# eib.net
KiCad netlist of a schematic drawn in EAGLE
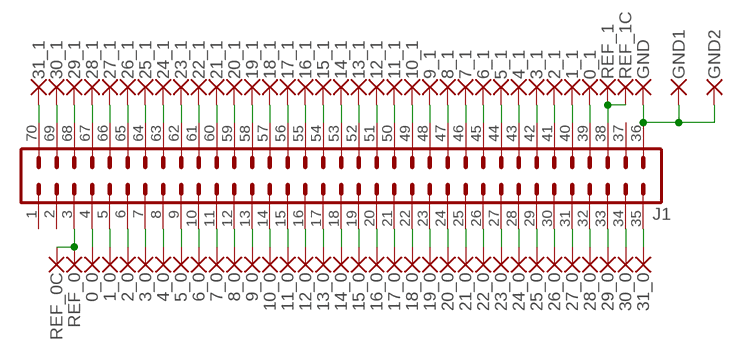
[diagram p0: schematic, sheet 1]

(export (version "E")
  (design (tool "Eeschema 10.0.6"))
  (components
    (comp (ref "0_0")
      (value "PAD_20_37")
      (footprint "eagle-import:PAD_20_37")
      (libsource (lib "eagle-import") (part "PAD_20_37"))
    )
    (comp (ref "0_1")
      (value "PAD_20_37")
      (footprint "eagle-import:PAD_20_37")
      (libsource (lib "eagle-import") (part "PAD_20_37"))
    )
    (comp (ref "1_0")
      (value "PAD_20_37")
      (footprint "eagle-import:PAD_20_37")
      (libsource (lib "eagle-import") (part "PAD_20_37"))
    )
    (comp (ref "1_1")
      (value "PAD_20_37")
      (footprint "eagle-import:PAD_20_37")
      (libsource (lib "eagle-import") (part "PAD_20_37"))
    )
    (comp (ref "2_0")
      (value "PAD_20_37")
      (footprint "eagle-import:PAD_20_37")
      (libsource (lib "eagle-import") (part "PAD_20_37"))
    )
    (comp (ref "2_1")
      (value "PAD_20_37")
      (footprint "eagle-import:PAD_20_37")
      (libsource (lib "eagle-import") (part "PAD_20_37"))
    )
    (comp (ref "3_0")
      (value "PAD_20_37")
      (footprint "eagle-import:PAD_20_37")
      (libsource (lib "eagle-import") (part "PAD_20_37"))
    )
    (comp (ref "3_1")
      (value "PAD_20_37")
      (footprint "eagle-import:PAD_20_37")
      (libsource (lib "eagle-import") (part "PAD_20_37"))
    )
    (comp (ref "4_0")
      (value "PAD_20_37")
      (footprint "eagle-import:PAD_20_37")
      (libsource (lib "eagle-import") (part "PAD_20_37"))
    )
    (comp (ref "4_1")
      (value "PAD_20_37")
      (footprint "eagle-import:PAD_20_37")
      (libsource (lib "eagle-import") (part "PAD_20_37"))
    )
    (comp (ref "5_0")
      (value "PAD_20_37")
      (footprint "eagle-import:PAD_20_37")
      (libsource (lib "eagle-import") (part "PAD_20_37"))
    )
    (comp (ref "5_1")
      (value "PAD_20_37")
      (footprint "eagle-import:PAD_20_37")
      (libsource (lib "eagle-import") (part "PAD_20_37"))
    )
    (comp (ref "6_0")
      (value "PAD_20_37")
      (footprint "eagle-import:PAD_20_37")
      (libsource (lib "eagle-import") (part "PAD_20_37"))
    )
    (comp (ref "6_1")
      (value "PAD_20_37")
      (footprint "eagle-import:PAD_20_37")
      (libsource (lib "eagle-import") (part "PAD_20_37"))
    )
    (comp (ref "7_0")
      (value "PAD_20_37")
      (footprint "eagle-import:PAD_20_37")
      (libsource (lib "eagle-import") (part "PAD_20_37"))
    )
    (comp (ref "7_1")
      (value "PAD_20_37")
      (footprint "eagle-import:PAD_20_37")
      (libsource (lib "eagle-import") (part "PAD_20_37"))
    )
    (comp (ref "8_0")
      (value "PAD_20_37")
      (footprint "eagle-import:PAD_20_37")
      (libsource (lib "eagle-import") (part "PAD_20_37"))
    )
    (comp (ref "8_1")
      (value "PAD_20_37")
      (footprint "eagle-import:PAD_20_37")
      (libsource (lib "eagle-import") (part "PAD_20_37"))
    )
    (comp (ref "9_0")
      (value "PAD_20_37")
      (footprint "eagle-import:PAD_20_37")
      (libsource (lib "eagle-import") (part "PAD_20_37"))
    )
    (comp (ref "9_1")
      (value "PAD_20_37")
      (footprint "eagle-import:PAD_20_37")
      (libsource (lib "eagle-import") (part "PAD_20_37"))
    )
    (comp (ref "10_0")
      (value "PAD_20_37")
      (footprint "eagle-import:PAD_20_37")
      (libsource (lib "eagle-import") (part "PAD_20_37"))
    )
    (comp (ref "10_1")
      (value "PAD_20_37")
      (footprint "eagle-import:PAD_20_37")
      (libsource (lib "eagle-import") (part "PAD_20_37"))
    )
    (comp (ref "11_0")
      (value "PAD_20_37")
      (footprint "eagle-import:PAD_20_37")
      (libsource (lib "eagle-import") (part "PAD_20_37"))
    )
    (comp (ref "11_1")
      (value "PAD_20_37")
      (footprint "eagle-import:PAD_20_37")
      (libsource (lib "eagle-import") (part "PAD_20_37"))
    )
    (comp (ref "12_0")
      (value "PAD_20_37")
      (footprint "eagle-import:PAD_20_37")
      (libsource (lib "eagle-import") (part "PAD_20_37"))
    )
    (comp (ref "12_1")
      (value "PAD_20_37")
      (footprint "eagle-import:PAD_20_37")
      (libsource (lib "eagle-import") (part "PAD_20_37"))
    )
    (comp (ref "13_0")
      (value "PAD_20_37")
      (footprint "eagle-import:PAD_20_37")
      (libsource (lib "eagle-import") (part "PAD_20_37"))
    )
    (comp (ref "13_1")
      (value "PAD_20_37")
      (footprint "eagle-import:PAD_20_37")
      (libsource (lib "eagle-import") (part "PAD_20_37"))
    )
    (comp (ref "14_0")
      (value "PAD_20_37")
      (footprint "eagle-import:PAD_20_37")
      (libsource (lib "eagle-import") (part "PAD_20_37"))
    )
    (comp (ref "14_1")
      (value "PAD_20_37")
      (footprint "eagle-import:PAD_20_37")
      (libsource (lib "eagle-import") (part "PAD_20_37"))
    )
    (comp (ref "15_0")
      (value "PAD_20_37")
      (footprint "eagle-import:PAD_20_37")
      (libsource (lib "eagle-import") (part "PAD_20_37"))
    )
    (comp (ref "15_1")
      (value "PAD_20_37")
      (footprint "eagle-import:PAD_20_37")
      (libsource (lib "eagle-import") (part "PAD_20_37"))
    )
    (comp (ref "16_0")
      (value "PAD_20_37")
      (footprint "eagle-import:PAD_20_37")
      (libsource (lib "eagle-import") (part "PAD_20_37"))
    )
    (comp (ref "16_1")
      (value "PAD_20_37")
      (footprint "eagle-import:PAD_20_37")
      (libsource (lib "eagle-import") (part "PAD_20_37"))
    )
    (comp (ref "17_0")
      (value "PAD_20_37")
      (footprint "eagle-import:PAD_20_37")
      (libsource (lib "eagle-import") (part "PAD_20_37"))
    )
    (comp (ref "17_1")
      (value "PAD_20_37")
      (footprint "eagle-import:PAD_20_37")
      (libsource (lib "eagle-import") (part "PAD_20_37"))
    )
    (comp (ref "18_0")
      (value "PAD_20_37")
      (footprint "eagle-import:PAD_20_37")
      (libsource (lib "eagle-import") (part "PAD_20_37"))
    )
    (comp (ref "18_1")
      (value "PAD_20_37")
      (footprint "eagle-import:PAD_20_37")
      (libsource (lib "eagle-import") (part "PAD_20_37"))
    )
    (comp (ref "19_0")
      (value "PAD_20_37")
      (footprint "eagle-import:PAD_20_37")
      (libsource (lib "eagle-import") (part "PAD_20_37"))
    )
    (comp (ref "19_1")
      (value "PAD_20_37")
      (footprint "eagle-import:PAD_20_37")
      (libsource (lib "eagle-import") (part "PAD_20_37"))
    )
    (comp (ref "20_0")
      (value "PAD_20_37")
      (footprint "eagle-import:PAD_20_37")
      (libsource (lib "eagle-import") (part "PAD_20_37"))
    )
    (comp (ref "20_1")
      (value "PAD_20_37")
      (footprint "eagle-import:PAD_20_37")
      (libsource (lib "eagle-import") (part "PAD_20_37"))
    )
    (comp (ref "21_0")
      (value "PAD_20_37")
      (footprint "eagle-import:PAD_20_37")
      (libsource (lib "eagle-import") (part "PAD_20_37"))
    )
    (comp (ref "21_1")
      (value "PAD_20_37")
      (footprint "eagle-import:PAD_20_37")
      (libsource (lib "eagle-import") (part "PAD_20_37"))
    )
    (comp (ref "22_0")
      (value "PAD_20_37")
      (footprint "eagle-import:PAD_20_37")
      (libsource (lib "eagle-import") (part "PAD_20_37"))
    )
    (comp (ref "22_1")
      (value "PAD_20_37")
      (footprint "eagle-import:PAD_20_37")
      (libsource (lib "eagle-import") (part "PAD_20_37"))
    )
    (comp (ref "23_0")
      (value "PAD_20_37")
      (footprint "eagle-import:PAD_20_37")
      (libsource (lib "eagle-import") (part "PAD_20_37"))
    )
    (comp (ref "23_1")
      (value "PAD_20_37")
      (footprint "eagle-import:PAD_20_37")
      (libsource (lib "eagle-import") (part "PAD_20_37"))
    )
    (comp (ref "24_0")
      (value "PAD_20_37")
      (footprint "eagle-import:PAD_20_37")
      (libsource (lib "eagle-import") (part "PAD_20_37"))
    )
    (comp (ref "24_1")
      (value "PAD_20_37")
      (footprint "eagle-import:PAD_20_37")
      (libsource (lib "eagle-import") (part "PAD_20_37"))
    )
    (comp (ref "25_0")
      (value "PAD_20_37")
      (footprint "eagle-import:PAD_20_37")
      (libsource (lib "eagle-import") (part "PAD_20_37"))
    )
    (comp (ref "25_1")
      (value "PAD_20_37")
      (footprint "eagle-import:PAD_20_37")
      (libsource (lib "eagle-import") (part "PAD_20_37"))
    )
    (comp (ref "26_0")
      (value "PAD_20_37")
      (footprint "eagle-import:PAD_20_37")
      (libsource (lib "eagle-import") (part "PAD_20_37"))
    )
    (comp (ref "26_1")
      (value "PAD_20_37")
      (footprint "eagle-import:PAD_20_37")
      (libsource (lib "eagle-import") (part "PAD_20_37"))
    )
    (comp (ref "27_0")
      (value "PAD_20_37")
      (footprint "eagle-import:PAD_20_37")
      (libsource (lib "eagle-import") (part "PAD_20_37"))
    )
    (comp (ref "27_1")
      (value "PAD_20_37")
      (footprint "eagle-import:PAD_20_37")
      (libsource (lib "eagle-import") (part "PAD_20_37"))
    )
    (comp (ref "28_0")
      (value "PAD_20_37")
      (footprint "eagle-import:PAD_20_37")
      (libsource (lib "eagle-import") (part "PAD_20_37"))
    )
    (comp (ref "28_1")
      (value "PAD_20_37")
      (footprint "eagle-import:PAD_20_37")
      (libsource (lib "eagle-import") (part "PAD_20_37"))
    )
    (comp (ref "29_0")
      (value "PAD_20_37")
      (footprint "eagle-import:PAD_20_37")
      (libsource (lib "eagle-import") (part "PAD_20_37"))
    )
    (comp (ref "29_1")
      (value "PAD_20_37")
      (footprint "eagle-import:PAD_20_37")
      (libsource (lib "eagle-import") (part "PAD_20_37"))
    )
    (comp (ref "30_0")
      (value "PAD_20_37")
      (footprint "eagle-import:PAD_20_37")
      (libsource (lib "eagle-import") (part "PAD_20_37"))
    )
    (comp (ref "30_1")
      (value "PAD_20_37")
      (footprint "eagle-import:PAD_20_37")
      (libsource (lib "eagle-import") (part "PAD_20_37"))
    )
    (comp (ref "31_0")
      (value "PAD_20_37")
      (footprint "eagle-import:PAD_20_37")
      (libsource (lib "eagle-import") (part "PAD_20_37"))
    )
    (comp (ref "31_1")
      (value "PAD_20_37")
      (footprint "eagle-import:PAD_20_37")
      (libsource (lib "eagle-import") (part "PAD_20_37"))
    )
    (comp (ref "GND")
      (value "PAD_20_37")
      (footprint "eagle-import:PAD_20_37")
      (libsource (lib "eagle-import") (part "PAD_20_37"))
    )
    (comp (ref "GND1")
      (value "PAD_20_37")
      (footprint "eagle-import:PAD_20_37")
      (libsource (lib "eagle-import") (part "PAD_20_37"))
    )
    (comp (ref "GND2")
      (value "PAD_20_37")
      (footprint "eagle-import:PAD_20_37")
      (libsource (lib "eagle-import") (part "PAD_20_37"))
    )
    (comp (ref "J1")
      (value "HIROSE_DF40-70DS")
      (footprint "eagle-import:HIROSE_DF40C-70DS")
      (libsource (lib "eagle-import") (part "HIROSE_DF40-70DS"))
    )
    (comp (ref "REF_0")
      (value "PAD_20_37")
      (footprint "eagle-import:PAD_20_37")
      (libsource (lib "eagle-import") (part "PAD_20_37"))
    )
    (comp (ref "REF_0C")
      (value "PAD_20_37")
      (footprint "eagle-import:PAD_20_37")
      (libsource (lib "eagle-import") (part "PAD_20_37"))
    )
    (comp (ref "REF_1")
      (value "PAD_20_37")
      (footprint "eagle-import:PAD_20_37")
      (libsource (lib "eagle-import") (part "PAD_20_37"))
    )
    (comp (ref "REF_1C")
      (value "PAD_20_37")
      (footprint "eagle-import:PAD_20_37")
      (libsource (lib "eagle-import") (part "PAD_20_37"))
    )
  )
  (nets
    (net (code "1") (name "Net-(0_0-P)") (class "Default")
      (node (ref "0_0") (pin "1") (pinfunction "P_1") (pintype "passive"))
      (node (ref "J1") (pin "4") (pinfunction "4_4") (pintype "passive"))
    )
    (net (code "2") (name "Net-(0_1-P)") (class "Default")
      (node (ref "0_1") (pin "1") (pinfunction "P_1") (pintype "passive"))
      (node (ref "J1") (pin "39") (pinfunction "39_39") (pintype "passive"))
    )
    (net (code "3") (name "Net-(1_0-P)") (class "Default")
      (node (ref "1_0") (pin "1") (pinfunction "P_1") (pintype "passive"))
      (node (ref "J1") (pin "5") (pinfunction "5_5") (pintype "passive"))
    )
    (net (code "4") (name "Net-(1_1-P)") (class "Default")
      (node (ref "1_1") (pin "1") (pinfunction "P_1") (pintype "passive"))
      (node (ref "J1") (pin "40") (pinfunction "40_40") (pintype "passive"))
    )
    (net (code "5") (name "Net-(2_0-P)") (class "Default")
      (node (ref "2_0") (pin "1") (pinfunction "P_1") (pintype "passive"))
      (node (ref "J1") (pin "6") (pinfunction "6_6") (pintype "passive"))
    )
    (net (code "6") (name "Net-(2_1-P)") (class "Default")
      (node (ref "2_1") (pin "1") (pinfunction "P_1") (pintype "passive"))
      (node (ref "J1") (pin "41") (pinfunction "41_41") (pintype "passive"))
    )
    (net (code "7") (name "Net-(3_0-P)") (class "Default")
      (node (ref "3_0") (pin "1") (pinfunction "P_1") (pintype "passive"))
      (node (ref "J1") (pin "7") (pinfunction "7_7") (pintype "passive"))
    )
    (net (code "8") (name "Net-(3_1-P)") (class "Default")
      (node (ref "3_1") (pin "1") (pinfunction "P_1") (pintype "passive"))
      (node (ref "J1") (pin "42") (pinfunction "42_42") (pintype "passive"))
    )
    (net (code "9") (name "Net-(4_0-P)") (class "Default")
      (node (ref "4_0") (pin "1") (pinfunction "P_1") (pintype "passive"))
      (node (ref "J1") (pin "8") (pinfunction "8_8") (pintype "passive"))
    )
    (net (code "10") (name "Net-(4_1-P)") (class "Default")
      (node (ref "4_1") (pin "1") (pinfunction "P_1") (pintype "passive"))
      (node (ref "J1") (pin "43") (pinfunction "43_43") (pintype "passive"))
    )
    (net (code "11") (name "Net-(5_0-P)") (class "Default")
      (node (ref "5_0") (pin "1") (pinfunction "P_1") (pintype "passive"))
      (node (ref "J1") (pin "9") (pinfunction "9_9") (pintype "passive"))
    )
    (net (code "12") (name "Net-(5_1-P)") (class "Default")
      (node (ref "5_1") (pin "1") (pinfunction "P_1") (pintype "passive"))
      (node (ref "J1") (pin "44") (pinfunction "44_44") (pintype "passive"))
    )
    (net (code "13") (name "Net-(6_0-P)") (class "Default")
      (node (ref "6_0") (pin "1") (pinfunction "P_1") (pintype "passive"))
      (node (ref "J1") (pin "10") (pinfunction "10_10") (pintype "passive"))
    )
    (net (code "14") (name "Net-(6_1-P)") (class "Default")
      (node (ref "6_1") (pin "1") (pinfunction "P_1") (pintype "passive"))
      (node (ref "J1") (pin "45") (pinfunction "45_45") (pintype "passive"))
    )
    (net (code "15") (name "Net-(7_0-P)") (class "Default")
      (node (ref "7_0") (pin "1") (pinfunction "P_1") (pintype "passive"))
      (node (ref "J1") (pin "11") (pinfunction "11_11") (pintype "passive"))
    )
    (net (code "16") (name "Net-(7_1-P)") (class "Default")
      (node (ref "7_1") (pin "1") (pinfunction "P_1") (pintype "passive"))
      (node (ref "J1") (pin "46") (pinfunction "46_46") (pintype "passive"))
    )
    (net (code "17") (name "Net-(8_0-P)") (class "Default")
      (node (ref "8_0") (pin "1") (pinfunction "P_1") (pintype "passive"))
      (node (ref "J1") (pin "12") (pinfunction "12_12") (pintype "passive"))
    )
    (net (code "18") (name "Net-(8_1-P)") (class "Default")
      (node (ref "8_1") (pin "1") (pinfunction "P_1") (pintype "passive"))
      (node (ref "J1") (pin "47") (pinfunction "47_47") (pintype "passive"))
    )
    (net (code "19") (name "Net-(9_0-P)") (class "Default")
      (node (ref "9_0") (pin "1") (pinfunction "P_1") (pintype "passive"))
      (node (ref "J1") (pin "13") (pinfunction "13_13") (pintype "passive"))
    )
    (net (code "20") (name "Net-(9_1-P)") (class "Default")
      (node (ref "9_1") (pin "1") (pinfunction "P_1") (pintype "passive"))
      (node (ref "J1") (pin "48") (pinfunction "48_48") (pintype "passive"))
    )
    (net (code "21") (name "Net-(10_0-P)") (class "Default")
      (node (ref "10_0") (pin "1") (pinfunction "P_1") (pintype "passive"))
      (node (ref "J1") (pin "14") (pinfunction "14_14") (pintype "passive"))
    )
    (net (code "22") (name "Net-(10_1-P)") (class "Default")
      (node (ref "10_1") (pin "1") (pinfunction "P_1") (pintype "passive"))
      (node (ref "J1") (pin "49") (pinfunction "49_49") (pintype "passive"))
    )
    (net (code "23") (name "Net-(11_0-P)") (class "Default")
      (node (ref "11_0") (pin "1") (pinfunction "P_1") (pintype "passive"))
      (node (ref "J1") (pin "15") (pinfunction "15_15") (pintype "passive"))
    )
    (net (code "24") (name "Net-(11_1-P)") (class "Default")
      (node (ref "11_1") (pin "1") (pinfunction "P_1") (pintype "passive"))
      (node (ref "J1") (pin "50") (pinfunction "50_50") (pintype "passive"))
    )
    (net (code "25") (name "Net-(12_0-P)") (class "Default")
      (node (ref "12_0") (pin "1") (pinfunction "P_1") (pintype "passive"))
      (node (ref "J1") (pin "16") (pinfunction "16_16") (pintype "passive"))
    )
    (net (code "26") (name "Net-(12_1-P)") (class "Default")
      (node (ref "12_1") (pin "1") (pinfunction "P_1") (pintype "passive"))
      (node (ref "J1") (pin "51") (pinfunction "51_51") (pintype "passive"))
    )
    (net (code "27") (name "Net-(13_0-P)") (class "Default")
      (node (ref "13_0") (pin "1") (pinfunction "P_1") (pintype "passive"))
      (node (ref "J1") (pin "17") (pinfunction "17_17") (pintype "passive"))
    )
    (net (code "28") (name "Net-(13_1-P)") (class "Default")
      (node (ref "13_1") (pin "1") (pinfunction "P_1") (pintype "passive"))
      (node (ref "J1") (pin "52") (pinfunction "52_52") (pintype "passive"))
    )
    (net (code "29") (name "Net-(14_0-P)") (class "Default")
      (node (ref "14_0") (pin "1") (pinfunction "P_1") (pintype "passive"))
      (node (ref "J1") (pin "18") (pinfunction "18_18") (pintype "passive"))
    )
    (net (code "30") (name "Net-(14_1-P)") (class "Default")
      (node (ref "14_1") (pin "1") (pinfunction "P_1") (pintype "passive"))
      (node (ref "J1") (pin "53") (pinfunction "53_53") (pintype "passive"))
    )
    (net (code "31") (name "Net-(15_0-P)") (class "Default")
      (node (ref "15_0") (pin "1") (pinfunction "P_1") (pintype "passive"))
      (node (ref "J1") (pin "19") (pinfunction "19_19") (pintype "passive"))
    )
    (net (code "32") (name "Net-(15_1-P)") (class "Default")
      (node (ref "15_1") (pin "1") (pinfunction "P_1") (pintype "passive"))
      (node (ref "J1") (pin "54") (pinfunction "54_54") (pintype "passive"))
    )
    (net (code "33") (name "Net-(16_0-P)") (class "Default")
      (node (ref "16_0") (pin "1") (pinfunction "P_1") (pintype "passive"))
      (node (ref "J1") (pin "20") (pinfunction "20_20") (pintype "passive"))
    )
    (net (code "34") (name "Net-(16_1-P)") (class "Default")
      (node (ref "16_1") (pin "1") (pinfunction "P_1") (pintype "passive"))
      (node (ref "J1") (pin "55") (pinfunction "55_55") (pintype "passive"))
    )
    (net (code "35") (name "Net-(17_0-P)") (class "Default")
      (node (ref "17_0") (pin "1") (pinfunction "P_1") (pintype "passive"))
      (node (ref "J1") (pin "21") (pinfunction "21_21") (pintype "passive"))
    )
    (net (code "36") (name "Net-(17_1-P)") (class "Default")
      (node (ref "17_1") (pin "1") (pinfunction "P_1") (pintype "passive"))
      (node (ref "J1") (pin "56") (pinfunction "56_56") (pintype "passive"))
    )
    (net (code "37") (name "Net-(18_0-P)") (class "Default")
      (node (ref "18_0") (pin "1") (pinfunction "P_1") (pintype "passive"))
      (node (ref "J1") (pin "22") (pinfunction "22_22") (pintype "passive"))
    )
    (net (code "38") (name "Net-(18_1-P)") (class "Default")
      (node (ref "18_1") (pin "1") (pinfunction "P_1") (pintype "passive"))
      (node (ref "J1") (pin "57") (pinfunction "57_57") (pintype "passive"))
    )
    (net (code "39") (name "Net-(19_0-P)") (class "Default")
      (node (ref "19_0") (pin "1") (pinfunction "P_1") (pintype "passive"))
      (node (ref "J1") (pin "23") (pinfunction "23_23") (pintype "passive"))
    )
    (net (code "40") (name "Net-(19_1-P)") (class "Default")
      (node (ref "19_1") (pin "1") (pinfunction "P_1") (pintype "passive"))
      (node (ref "J1") (pin "58") (pinfunction "58_58") (pintype "passive"))
    )
    (net (code "41") (name "Net-(20_0-P)") (class "Default")
      (node (ref "20_0") (pin "1") (pinfunction "P_1") (pintype "passive"))
      (node (ref "J1") (pin "24") (pinfunction "24_24") (pintype "passive"))
    )
    (net (code "42") (name "Net-(20_1-P)") (class "Default")
      (node (ref "20_1") (pin "1") (pinfunction "P_1") (pintype "passive"))
      (node (ref "J1") (pin "59") (pinfunction "59_59") (pintype "passive"))
    )
    (net (code "43") (name "Net-(21_0-P)") (class "Default")
      (node (ref "21_0") (pin "1") (pinfunction "P_1") (pintype "passive"))
      (node (ref "J1") (pin "25") (pinfunction "25_25") (pintype "passive"))
    )
    (net (code "44") (name "Net-(21_1-P)") (class "Default")
      (node (ref "21_1") (pin "1") (pinfunction "P_1") (pintype "passive"))
      (node (ref "J1") (pin "60") (pinfunction "60_60") (pintype "passive"))
    )
    (net (code "45") (name "Net-(22_0-P)") (class "Default")
      (node (ref "22_0") (pin "1") (pinfunction "P_1") (pintype "passive"))
      (node (ref "J1") (pin "26") (pinfunction "26_26") (pintype "passive"))
    )
    (net (code "46") (name "Net-(22_1-P)") (class "Default")
      (node (ref "22_1") (pin "1") (pinfunction "P_1") (pintype "passive"))
      (node (ref "J1") (pin "61") (pinfunction "61_61") (pintype "passive"))
    )
    (net (code "47") (name "Net-(23_0-P)") (class "Default")
      (node (ref "23_0") (pin "1") (pinfunction "P_1") (pintype "passive"))
      (node (ref "J1") (pin "27") (pinfunction "27_27") (pintype "passive"))
    )
    (net (code "48") (name "Net-(23_1-P)") (class "Default")
      (node (ref "23_1") (pin "1") (pinfunction "P_1") (pintype "passive"))
      (node (ref "J1") (pin "62") (pinfunction "62_62") (pintype "passive"))
    )
    (net (code "49") (name "Net-(24_0-P)") (class "Default")
      (node (ref "24_0") (pin "1") (pinfunction "P_1") (pintype "passive"))
      (node (ref "J1") (pin "28") (pinfunction "28_28") (pintype "passive"))
    )
    (net (code "50") (name "Net-(24_1-P)") (class "Default")
      (node (ref "24_1") (pin "1") (pinfunction "P_1") (pintype "passive"))
      (node (ref "J1") (pin "63") (pinfunction "63_63") (pintype "passive"))
    )
    (net (code "51") (name "Net-(25_0-P)") (class "Default")
      (node (ref "25_0") (pin "1") (pinfunction "P_1") (pintype "passive"))
      (node (ref "J1") (pin "29") (pinfunction "29_29") (pintype "passive"))
    )
    (net (code "52") (name "Net-(25_1-P)") (class "Default")
      (node (ref "25_1") (pin "1") (pinfunction "P_1") (pintype "passive"))
      (node (ref "J1") (pin "64") (pinfunction "64_64") (pintype "passive"))
    )
    (net (code "53") (name "Net-(26_0-P)") (class "Default")
      (node (ref "26_0") (pin "1") (pinfunction "P_1") (pintype "passive"))
      (node (ref "J1") (pin "30") (pinfunction "30_30") (pintype "passive"))
    )
    (net (code "54") (name "Net-(26_1-P)") (class "Default")
      (node (ref "26_1") (pin "1") (pinfunction "P_1") (pintype "passive"))
      (node (ref "J1") (pin "65") (pinfunction "65_65") (pintype "passive"))
    )
    (net (code "55") (name "Net-(27_0-P)") (class "Default")
      (node (ref "27_0") (pin "1") (pinfunction "P_1") (pintype "passive"))
      (node (ref "J1") (pin "31") (pinfunction "31_31") (pintype "passive"))
    )
    (net (code "56") (name "Net-(27_1-P)") (class "Default")
      (node (ref "27_1") (pin "1") (pinfunction "P_1") (pintype "passive"))
      (node (ref "J1") (pin "66") (pinfunction "66_66") (pintype "passive"))
    )
    (net (code "57") (name "Net-(28_0-P)") (class "Default")
      (node (ref "28_0") (pin "1") (pinfunction "P_1") (pintype "passive"))
      (node (ref "J1") (pin "32") (pinfunction "32_32") (pintype "passive"))
    )
    (net (code "58") (name "Net-(28_1-P)") (class "Default")
      (node (ref "28_1") (pin "1") (pinfunction "P_1") (pintype "passive"))
      (node (ref "J1") (pin "67") (pinfunction "67_67") (pintype "passive"))
    )
    (net (code "59") (name "Net-(29_0-P)") (class "Default")
      (node (ref "29_0") (pin "1") (pinfunction "P_1") (pintype "passive"))
      (node (ref "J1") (pin "33") (pinfunction "33_33") (pintype "passive"))
    )
    (net (code "60") (name "Net-(29_1-P)") (class "Default")
      (node (ref "29_1") (pin "1") (pinfunction "P_1") (pintype "passive"))
      (node (ref "J1") (pin "68") (pinfunction "68_68") (pintype "passive"))
    )
    (net (code "61") (name "Net-(30_0-P)") (class "Default")
      (node (ref "30_0") (pin "1") (pinfunction "P_1") (pintype "passive"))
      (node (ref "J1") (pin "34") (pinfunction "34_34") (pintype "passive"))
    )
    (net (code "62") (name "Net-(30_1-P)") (class "Default")
      (node (ref "30_1") (pin "1") (pinfunction "P_1") (pintype "passive"))
      (node (ref "J1") (pin "69") (pinfunction "69_69") (pintype "passive"))
    )
    (net (code "63") (name "Net-(31_0-P)") (class "Default")
      (node (ref "31_0") (pin "1") (pinfunction "P_1") (pintype "passive"))
      (node (ref "J1") (pin "35") (pinfunction "35_35") (pintype "passive"))
    )
    (net (code "64") (name "Net-(31_1-P)") (class "Default")
      (node (ref "31_1") (pin "1") (pinfunction "P_1") (pintype "passive"))
      (node (ref "J1") (pin "70") (pinfunction "70_70") (pintype "passive"))
    )
    (net (code "65") (name "Net-(GND-P)") (class "Default")
      (node (ref "GND") (pin "1") (pinfunction "P_1") (pintype "passive"))
      (node (ref "GND1") (pin "1") (pinfunction "P_1") (pintype "passive"))
      (node (ref "GND2") (pin "1") (pinfunction "P_1") (pintype "passive"))
      (node (ref "J1") (pin "36") (pinfunction "36_36") (pintype "passive"))
    )
    (net (code "66") (name "Net-(REF_0-P)") (class "Default")
      (node (ref "J1") (pin "3") (pinfunction "3_3") (pintype "passive"))
      (node (ref "REF_0") (pin "1") (pinfunction "P_1") (pintype "passive"))
      (node (ref "REF_0C") (pin "1") (pinfunction "P_1") (pintype "passive"))
    )
    (net (code "67") (name "Net-(REF_1-P)") (class "Default")
      (node (ref "J1") (pin "38") (pinfunction "38_38") (pintype "passive"))
      (node (ref "REF_1") (pin "1") (pinfunction "P_1") (pintype "passive"))
      (node (ref "REF_1C") (pin "1") (pinfunction "P_1") (pintype "passive"))
    )
    (net (code "68") (name "unconnected-(J1-Pad1)") (class "Default")
      (node (ref "J1") (pin "1") (pinfunction "1_1") (pintype "passive"))
    )
    (net (code "69") (name "unconnected-(J1-Pad2)") (class "Default")
      (node (ref "J1") (pin "2") (pinfunction "2_2") (pintype "passive"))
    )
    (net (code "70") (name "unconnected-(J1-Pad37)") (class "Default")
      (node (ref "J1") (pin "37") (pinfunction "37_37") (pintype "passive"))
    )
  )
)
